# Schematic.net
KiCad netlist of a schematic drawn in Altium Designer
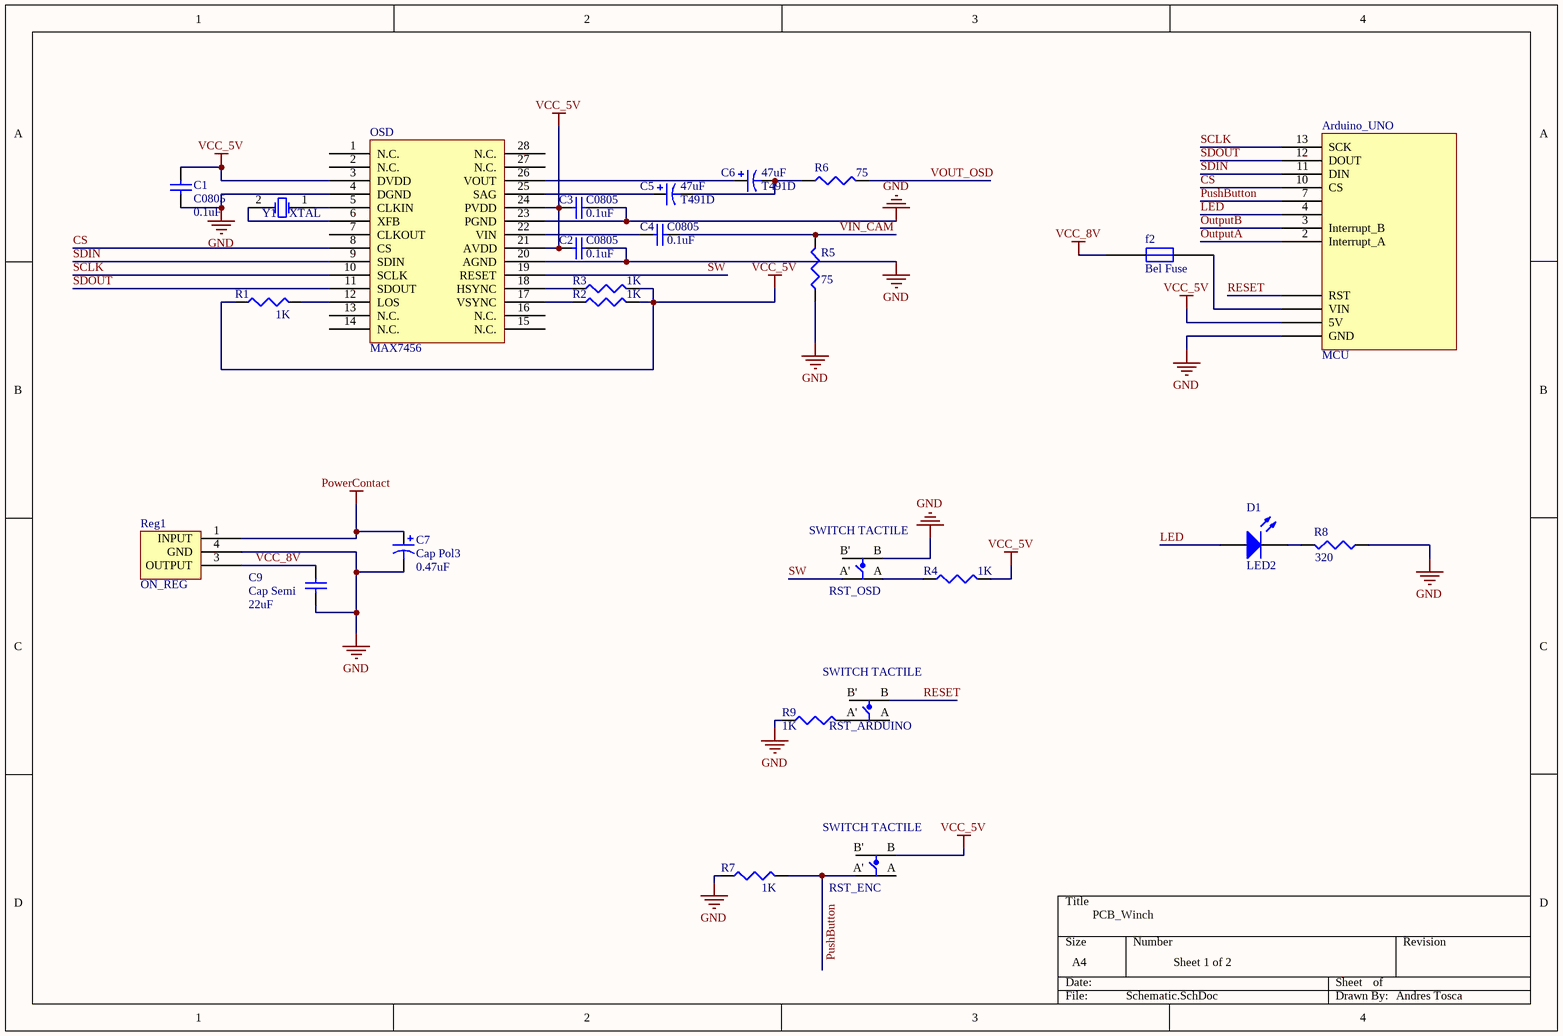
[diagram p0: Schematic.SchDoc]

(export (version "E")
  (design (tool "Eeschema 10.0.6"))
  (components
    (comp (ref "Arduino_UNO") (value "MCU") (footprint "MCU") (libsource (lib "Schlib") (part "MCU")))
    (comp (ref "C1")
      (value "C0805")
      (footprint "CAP_KEMET0.1UF")
      (description "Ceramic Chip Capacitor - Standard")
      (fields (field (name "ALTIUM_VALUE") "0.1uF") (field (name "PUBLISHER") "Altium Limited"))
      (libsource (lib "KEMET Chip Capacitor") (part "C0805"))
    )
    (comp (ref "C2")
      (value "C0805")
      (footprint "CAP_KEMET0.1UF")
      (description "Ceramic Chip Capacitor - Standard")
      (fields (field (name "ALTIUM_VALUE") "0.1uF") (field (name "PUBLISHER") "Altium Limited"))
      (libsource (lib "KEMET Chip Capacitor") (part "C0805"))
    )
    (comp (ref "C3")
      (value "C0805")
      (footprint "CAP_KEMET0.1UF")
      (description "Ceramic Chip Capacitor - Standard")
      (fields (field (name "ALTIUM_VALUE") "0.1uF") (field (name "PUBLISHER") "Altium Limited"))
      (libsource (lib "KEMET Chip Capacitor") (part "C0805"))
    )
    (comp (ref "C4")
      (value "C0805")
      (footprint "CAP_KEMET0.1UF")
      (description "Ceramic Chip Capacitor - Standard")
      (fields (field (name "ALTIUM_VALUE") "0.1uF") (field (name "PUBLISHER") "Altium Limited"))
      (libsource (lib "KEMET Chip Capacitor") (part "C0805"))
    )
    (comp (ref "C5")
      (value "T491D")
      (footprint "CAP_Kemet47UF")
      (description "Solid Tantalum Chip Capacitor, Standard T491 Series - Industrial Grade")
      (fields (field (name "ALTIUM_VALUE") "47uF") (field (name "PUBLISHER") "Altium Limited"))
      (libsource (lib "KEMET Chip Capacitor") (part "T491D"))
    )
    (comp (ref "C6")
      (value "T491D")
      (footprint "CAP_Kemet47UF")
      (description "Solid Tantalum Chip Capacitor, Standard T491 Series - Industrial Grade")
      (fields (field (name "ALTIUM_VALUE") "47uF") (field (name "PUBLISHER") "Altium Limited"))
      (libsource (lib "KEMET Chip Capacitor") (part "T491D"))
    )
    (comp (ref "C7")
      (value "Cap Pol3")
      (footprint "C0805")
      (description "Polarized Capacitor (Surface Mount)")
      (fields (field (name "ALTIUM_VALUE") "0.47uF") (field (name "PUBLISHER") "Altium Limited"))
      (libsource (lib "Miscellaneous Devices") (part "Cap Pol3"))
    )
    (comp (ref "C9")
      (value "Cap Semi")
      (footprint "CAP_KEMET22UF")
      (description "Capacitor (Semiconductor SIM Model)")
      (fields (field (name "ALTIUM_VALUE") "22uF") (field (name "PUBLISHER") "Altium Limited"))
      (libsource (lib "Miscellaneous Devices") (part "Cap Semi"))
    )
    (comp (ref "D1")
      (value "LED2")
      (footprint "3.2X1.6X1.1")
      (description "Typical RED, GREEN, YELLOW, AMBER GaAs LED")
      (fields (field (name "PUBLISHER") "Altium Limited"))
      (libsource (lib "Miscellaneous Devices") (part "LED2"))
    )
    (comp (ref "f2") (value "Bel Fuse") (footprint "Bel_Fuse") (libsource (lib "Schlib") (part "Bel Fuse")))
    (comp (ref "OSD") (value "MAX7456") (libsource (lib "Schlib") (part "MAX7456")))
    (comp (ref "R1")
      (value "1K")
      (footprint "RESC2012")
      (description "Resistor")
      (fields (field (name "Comment") "Res3") (field (name "PUBLISHER") "Altium Limited"))
      (libsource (lib "Miscellaneous Devices") (part "Res3"))
    )
    (comp (ref "R2")
      (value "1K")
      (footprint "RESC2012")
      (description "Resistor")
      (fields (field (name "Comment") "Res3") (field (name "PUBLISHER") "Altium Limited"))
      (libsource (lib "Miscellaneous Devices") (part "Res3"))
    )
    (comp (ref "R3")
      (value "1K")
      (footprint "RESC2012")
      (description "Resistor")
      (fields (field (name "Comment") "Res3") (field (name "PUBLISHER") "Altium Limited"))
      (libsource (lib "Miscellaneous Devices") (part "Res3"))
    )
    (comp (ref "R4")
      (value "1K")
      (footprint "RESC2012")
      (description "Resistor")
      (fields (field (name "Comment") "Res3") (field (name "PUBLISHER") "Altium Limited"))
      (libsource (lib "Miscellaneous Devices") (part "Res3"))
    )
    (comp (ref "R5")
      (value "75")
      (footprint "RESC2012")
      (description "Resistor")
      (fields (field (name "Comment") "Res3") (field (name "PUBLISHER") "Altium Limited"))
      (libsource (lib "Miscellaneous Devices") (part "Res3"))
    )
    (comp (ref "R6")
      (value "75")
      (footprint "RESC2012")
      (description "Resistor")
      (fields (field (name "Comment") "Res3") (field (name "PUBLISHER") "Altium Limited"))
      (libsource (lib "Miscellaneous Devices") (part "Res3"))
    )
    (comp (ref "R7")
      (value "1K")
      (footprint "RESC2012")
      (description "Resistor")
      (fields (field (name "Comment") "Res3") (field (name "PUBLISHER") "Altium Limited"))
      (libsource (lib "Miscellaneous Devices") (part "Res3"))
    )
    (comp (ref "R8")
      (value "320")
      (footprint "RESC2012")
      (description "Resistor")
      (fields (field (name "Comment") "Res3") (field (name "PUBLISHER") "Altium Limited"))
      (libsource (lib "Miscellaneous Devices") (part "Res3"))
    )
    (comp (ref "R9")
      (value "1K")
      (footprint "RESC2012")
      (description "Resistor")
      (fields (field (name "Comment") "Res3") (field (name "PUBLISHER") "Altium Limited"))
      (libsource (lib "Miscellaneous Devices") (part "Res3"))
    )
    (comp (ref "Reg1")
      (value "ON_REG")
      (footprint "SOT223_LM2940")
      (libsource (lib "Schlib") (part "ON_REG"))
    )
    (comp (ref "RST_ARDUINO")
      (value "SWITCH TACTILE")
      (footprint "Switch tactile")
      (libsource (lib "Schlib") (part "SWITCH TACTILE"))
    )
    (comp (ref "RST_ENC")
      (value "SWITCH TACTILE")
      (footprint "Switch tactile")
      (libsource (lib "Schlib") (part "SWITCH TACTILE"))
    )
    (comp (ref "RST_OSD")
      (value "SWITCH TACTILE")
      (footprint "Switch tactile")
      (libsource (lib "Schlib") (part "SWITCH TACTILE"))
    )
    (comp (ref "Y1")
      (value "XTAL")
      (footprint "ABM3-27.000MHZ-D2Y-T")
      (description "Crystal Oscillator")
      (fields (field (name "PUBLISHER") "Altium Limited"))
      (libsource (lib "Miscellaneous Devices") (part "XTAL"))
    )
  )
  (nets
    (net (code "1") (name "/CS") (class "Default")
      (node (ref "Arduino_UNO") (pin "10") (pinfunction "CS_10") (pintype "passive"))
      (node (ref "OSD") (pin "8") (pinfunction "CS_8") (pintype "passive"))
    )
    (net (code "2") (name "/LED") (class "Default")
      (node (ref "Arduino_UNO") (pin "4") (pinfunction "LED_4") (pintype "passive"))
      (node (ref "D1") (pin "1") (pinfunction "A_1") (pintype "passive"))
    )
    (net (code "3") (name "/OutputA") (class "Default")
      (node (ref "Arduino_UNO") (pin "2") (pinfunction "Interrupt_A_2") (pintype "passive"))
    )
    (net (code "4") (name "/OutputB") (class "Default")
      (node (ref "Arduino_UNO") (pin "3") (pinfunction "Interrupt_B_3") (pintype "passive"))
    )
    (net (code "5") (name "/PushButton") (class "Default")
      (node (ref "Arduino_UNO") (pin "7") (pinfunction "VIN_7") (pintype "passive"))
      (node (ref "R7") (pin "2") (pinfunction "2_2") (pintype "passive"))
      (node (ref "RST_ENC") (pin "A'") (pinfunction "A'_A'") (pintype "passive"))
    )
    (net (code "6") (name "/RESET") (class "Default")
      (node (ref "Arduino_UNO") (pin "RST") (pinfunction "RST_RST") (pintype "passive"))
      (node (ref "RST_ARDUINO") (pin "B") (pinfunction "B_B") (pintype "passive"))
    )
    (net (code "7") (name "/SCLK") (class "Default")
      (node (ref "Arduino_UNO") (pin "13") (pinfunction "SCK_13") (pintype "passive"))
      (node (ref "OSD") (pin "10") (pinfunction "SCLK_10") (pintype "passive"))
    )
    (net (code "8") (name "/SDIN") (class "Default")
      (node (ref "Arduino_UNO") (pin "11") (pinfunction "DIN_11") (pintype "passive"))
      (node (ref "OSD") (pin "9") (pinfunction "SDIN_9") (pintype "passive"))
    )
    (net (code "9") (name "/SDOUT") (class "Default")
      (node (ref "Arduino_UNO") (pin "12") (pinfunction "DOUT_12") (pintype "passive"))
      (node (ref "OSD") (pin "11") (pinfunction "SDOUT_11") (pintype "passive"))
    )
    (net (code "10") (name "/SW") (class "Default")
      (node (ref "OSD") (pin "19") (pinfunction "RESET_19") (pintype "passive"))
      (node (ref "RST_OSD") (pin "A'") (pinfunction "A'_A'") (pintype "passive"))
    )
    (net (code "11") (name "/VIN_CAM") (class "Default")
      (node (ref "C4") (pin "2") (pinfunction "2_2") (pintype "passive"))
      (node (ref "R5") (pin "2") (pinfunction "2_2") (pintype "passive"))
    )
    (net (code "12") (name "/VOUT_OSD") (class "Default")
      (node (ref "R6") (pin "2") (pinfunction "2_2") (pintype "passive"))
    )
    (net (code "13") (name "GND") (class "Default")
      (node (ref "Arduino_UNO") (pin "GND") (pinfunction "GND_GND") (pintype "passive"))
      (node (ref "C1") (pin "2") (pinfunction "2_2") (pintype "passive"))
      (node (ref "C2") (pin "2") (pinfunction "2_2") (pintype "passive"))
      (node (ref "C3") (pin "2") (pinfunction "2_2") (pintype "passive"))
      (node (ref "C7") (pin "2") (pinfunction "2_2") (pintype "passive"))
      (node (ref "C9") (pin "1") (pinfunction "1_1") (pintype "passive"))
      (node (ref "OSD") (pin "20") (pinfunction "AGND_20") (pintype "passive"))
      (node (ref "OSD") (pin "23") (pinfunction "PGND_23") (pintype "passive"))
      (node (ref "OSD") (pin "4") (pinfunction "DGND_4") (pintype "passive"))
      (node (ref "R5") (pin "1") (pinfunction "1_1") (pintype "passive"))
      (node (ref "R7") (pin "1") (pinfunction "1_1") (pintype "passive"))
      (node (ref "R8") (pin "1") (pinfunction "1_1") (pintype "passive"))
      (node (ref "R9") (pin "1") (pinfunction "1_1") (pintype "passive"))
      (node (ref "RST_OSD") (pin "B") (pinfunction "B_B") (pintype "passive"))
      (node (ref "Reg1") (pin "4") (pinfunction "GND_4") (pintype "passive"))
    )
    (net (code "14") (name "Net-(Arduino_UNO-PadVIN)") (class "Default")
      (node (ref "Arduino_UNO") (pin "VIN") (pinfunction "VIN_VIN") (pintype "passive"))
      (node (ref "f2") (pin "2") (pinfunction "2_2") (pintype "passive"))
    )
    (net (code "15") (name "Net-(C5-Pad2)") (class "Default")
      (node (ref "C5") (pin "2") (pinfunction "2_2") (pintype "passive"))
      (node (ref "C6") (pin "2") (pinfunction "2_2") (pintype "passive"))
      (node (ref "R6") (pin "1") (pinfunction "1_1") (pintype "passive"))
    )
    (net (code "16") (name "Net-(D1-K)") (class "Default")
      (node (ref "D1") (pin "2") (pinfunction "K_2") (pintype "passive"))
      (node (ref "R8") (pin "2") (pinfunction "2_2") (pintype "passive"))
    )
    (net (code "17") (name "Net-(OSD-CLKIN)") (class "Default")
      (node (ref "OSD") (pin "5") (pinfunction "CLKIN_5") (pintype "passive"))
      (node (ref "Y1") (pin "1") (pinfunction "OSC1_1") (pintype "passive"))
    )
    (net (code "18") (name "Net-(OSD-HSYNC)") (class "Default")
      (node (ref "OSD") (pin "18") (pinfunction "HSYNC_18") (pintype "passive"))
      (node (ref "R3") (pin "1") (pinfunction "1_1") (pintype "passive"))
    )
    (net (code "19") (name "Net-(OSD-LOS)") (class "Default")
      (node (ref "OSD") (pin "12") (pinfunction "LOS_12") (pintype "passive"))
      (node (ref "R1") (pin "2") (pinfunction "2_2") (pintype "passive"))
    )
    (net (code "20") (name "Net-(OSD-SAG)") (class "Default")
      (node (ref "C5") (pin "1") (pinfunction "1_1") (pintype "passive"))
      (node (ref "OSD") (pin "25") (pinfunction "SAG_25") (pintype "passive"))
    )
    (net (code "21") (name "Net-(OSD-VIN)") (class "Default")
      (node (ref "C4") (pin "1") (pinfunction "1_1") (pintype "passive"))
      (node (ref "OSD") (pin "22") (pinfunction "VIN_22") (pintype "passive"))
    )
    (net (code "22") (name "Net-(OSD-VOUT)") (class "Default")
      (node (ref "C6") (pin "1") (pinfunction "1_1") (pintype "passive"))
      (node (ref "OSD") (pin "26") (pinfunction "VOUT_26") (pintype "passive"))
    )
    (net (code "23") (name "Net-(OSD-VSYNC)") (class "Default")
      (node (ref "OSD") (pin "17") (pinfunction "VSYNC_17") (pintype "passive"))
      (node (ref "R2") (pin "1") (pinfunction "1_1") (pintype "passive"))
    )
    (net (code "24") (name "Net-(OSD-XFB)") (class "Default")
      (node (ref "OSD") (pin "6") (pinfunction "XFB_6") (pintype "passive"))
      (node (ref "Y1") (pin "2") (pinfunction "OSC2_2") (pintype "passive"))
    )
    (net (code "25") (name "Net-(R4-Pad1)") (class "Default")
      (node (ref "R4") (pin "1") (pinfunction "1_1") (pintype "passive"))
      (node (ref "RST_OSD") (pin "A") (pinfunction "A_A") (pintype "passive"))
    )
    (net (code "26") (name "Net-(R9-Pad2)") (class "Default")
      (node (ref "R9") (pin "2") (pinfunction "2_2") (pintype "passive"))
      (node (ref "RST_ARDUINO") (pin "A'") (pinfunction "A'_A'") (pintype "passive"))
    )
    (net (code "27") (name "PowerContact") (class "Default")
      (node (ref "C7") (pin "1") (pinfunction "1_1") (pintype "passive"))
      (node (ref "Reg1") (pin "1") (pinfunction "INPUT_1") (pintype "passive"))
    )
    (net (code "28") (name "VCC_5V") (class "Default")
      (node (ref "Arduino_UNO") (pin "5V") (pinfunction "5V_5V") (pintype "passive"))
      (node (ref "C1") (pin "1") (pinfunction "1_1") (pintype "passive"))
      (node (ref "C2") (pin "1") (pinfunction "1_1") (pintype "passive"))
      (node (ref "C3") (pin "1") (pinfunction "1_1") (pintype "passive"))
      (node (ref "OSD") (pin "21") (pinfunction "AVDD_21") (pintype "passive"))
      (node (ref "OSD") (pin "24") (pinfunction "PVDD_24") (pintype "passive"))
      (node (ref "OSD") (pin "3") (pinfunction "DVDD_3") (pintype "passive"))
      (node (ref "R1") (pin "1") (pinfunction "1_1") (pintype "passive"))
      (node (ref "R2") (pin "2") (pinfunction "2_2") (pintype "passive"))
      (node (ref "R3") (pin "2") (pinfunction "2_2") (pintype "passive"))
      (node (ref "R4") (pin "2") (pinfunction "2_2") (pintype "passive"))
      (node (ref "RST_ENC") (pin "B") (pinfunction "B_B") (pintype "passive"))
    )
    (net (code "29") (name "VCC_8V") (class "Default")
      (node (ref "C9") (pin "2") (pinfunction "2_2") (pintype "passive"))
      (node (ref "Reg1") (pin "3") (pinfunction "OUTPUT_3") (pintype "passive"))
      (node (ref "f2") (pin "1") (pinfunction "1_1") (pintype "passive"))
    )
    (net (code "30") (name "unconnected-(OSD-CLKOUT-Pad7)") (class "Default")
      (node (ref "OSD") (pin "7") (pinfunction "CLKOUT_7") (pintype "passive"))
    )
    (net (code "31") (name "unconnected-(OSD-N.C.-Pad1)") (class "Default")
      (node (ref "OSD") (pin "1") (pinfunction "N.C._1") (pintype "passive"))
    )
    (net (code "32") (name "unconnected-(OSD-N.C.-Pad2)") (class "Default")
      (node (ref "OSD") (pin "2") (pinfunction "N.C._2") (pintype "passive"))
    )
    (net (code "33") (name "unconnected-(OSD-N.C.-Pad13)") (class "Default")
      (node (ref "OSD") (pin "13") (pinfunction "N.C._13") (pintype "passive"))
    )
    (net (code "34") (name "unconnected-(OSD-N.C.-Pad14)") (class "Default")
      (node (ref "OSD") (pin "14") (pinfunction "N.C._14") (pintype "passive"))
    )
    (net (code "35") (name "unconnected-(OSD-N.C.-Pad15)") (class "Default")
      (node (ref "OSD") (pin "15") (pinfunction "N.C._15") (pintype "passive"))
    )
    (net (code "36") (name "unconnected-(OSD-N.C.-Pad16)") (class "Default")
      (node (ref "OSD") (pin "16") (pinfunction "N.C._16") (pintype "passive"))
    )
    (net (code "37") (name "unconnected-(OSD-N.C.-Pad27)") (class "Default")
      (node (ref "OSD") (pin "27") (pinfunction "N.C._27") (pintype "passive"))
    )
    (net (code "38") (name "unconnected-(OSD-N.C.-Pad28)") (class "Default")
      (node (ref "OSD") (pin "28") (pinfunction "N.C._28") (pintype "passive"))
    )
    (net (code "39") (name "unconnected-(RST_ARDUINO-PadA)") (class "Default")
      (node (ref "RST_ARDUINO") (pin "A") (pinfunction "A_A") (pintype "passive"))
    )
    (net (code "40") (name "unconnected-(RST_ARDUINO-PadB')") (class "Default")
      (node (ref "RST_ARDUINO") (pin "B'") (pinfunction "B'_B'") (pintype "passive"))
    )
    (net (code "41") (name "unconnected-(RST_ENC-PadA)") (class "Default")
      (node (ref "RST_ENC") (pin "A") (pinfunction "A_A") (pintype "passive"))
    )
    (net (code "42") (name "unconnected-(RST_ENC-PadB')") (class "Default")
      (node (ref "RST_ENC") (pin "B'") (pinfunction "B'_B'") (pintype "passive"))
    )
    (net (code "43") (name "unconnected-(RST_OSD-PadB')") (class "Default")
      (node (ref "RST_OSD") (pin "B'") (pinfunction "B'_B'") (pintype "passive"))
    )
  )
)
